# Sheet1.net
KiCad netlist of a schematic drawn in Altium Designer
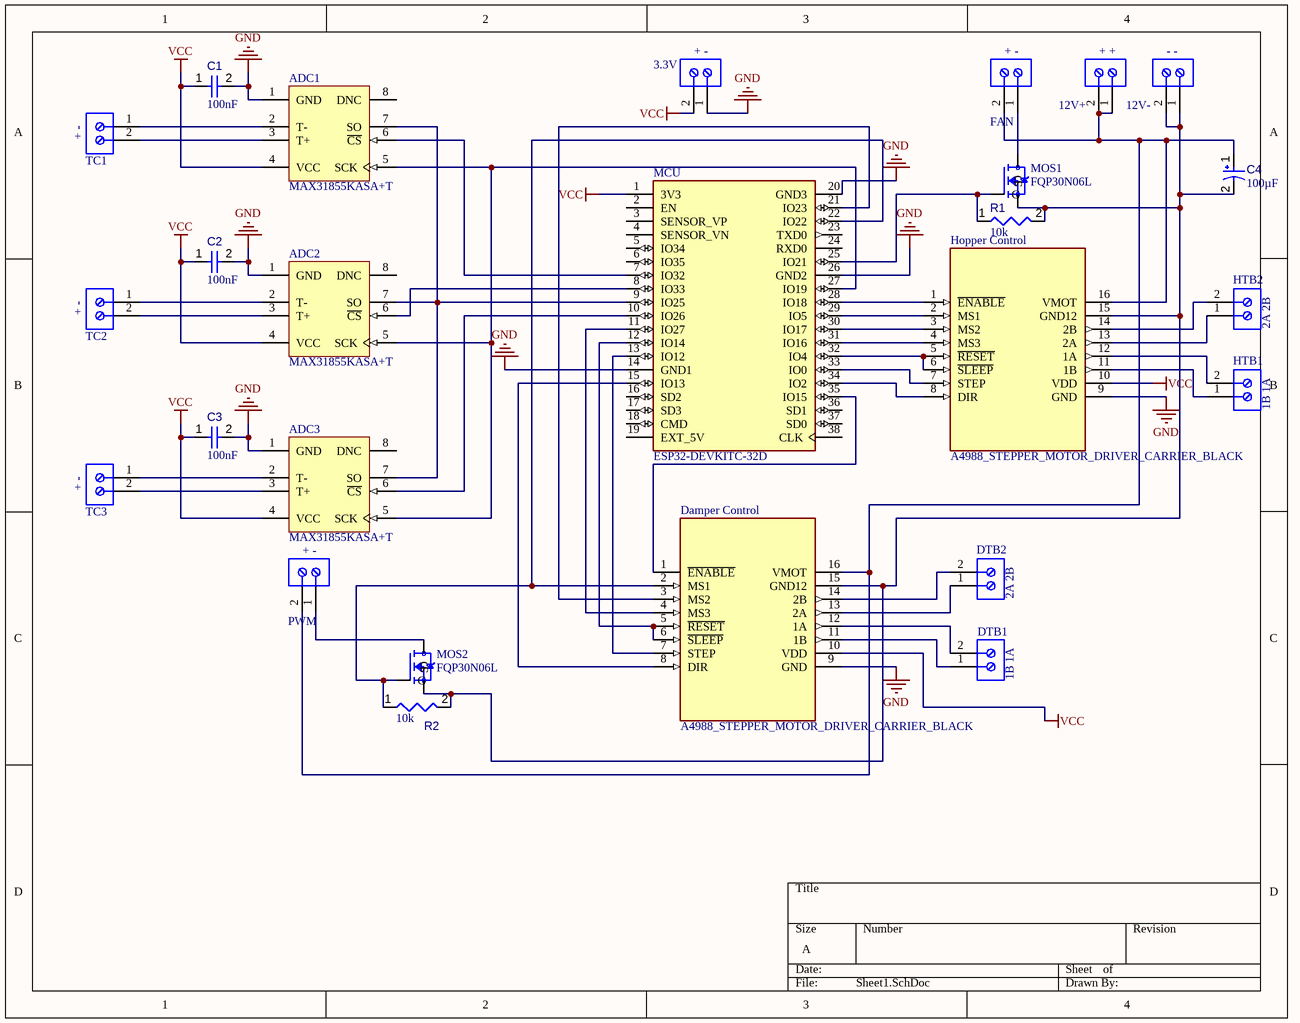
[diagram p0: Sheet1.SchDoc]

(export (version "E")
  (design (tool "Eeschema 10.0.6"))
  (components
    (comp (ref "3.3V")
      (value "+ -")
      (footprint "691103110002")
      (description "Series 1031 - 3.50 mm Horizontal Entry Modular with Pressure Clamp WR-TBL, 2 pin")
      (fields
        (field (name "MANUFACTURER") "Wurth Elektronik")
        (field (name "PART NUMBER") "691103110002")
        (field (name "PUBLISHER") "WurthElektronik")
      )
      (libsource (lib "Altium Content Vault") (part "WE-CN-1P-F-TB2"))
    )
    (comp (ref "12V+")
      (value "+ +")
      (footprint "691103110002")
      (description "Series 1031 - 3.50 mm Horizontal Entry Modular with Pressure Clamp WR-TBL, 2 pin")
      (fields
        (field (name "MANUFACTURER") "Wurth Elektronik")
        (field (name "PART NUMBER") "691103110002")
        (field (name "PUBLISHER") "WurthElektronik")
      )
      (libsource (lib "Altium Content Vault") (part "WE-CN-1P-F-TB2"))
    )
    (comp (ref "12V-")
      (value "- -")
      (footprint "691103110002")
      (description "Series 1031 - 3.50 mm Horizontal Entry Modular with Pressure Clamp WR-TBL, 2 pin")
      (fields
        (field (name "MANUFACTURER") "Wurth Elektronik")
        (field (name "PART NUMBER") "691103110002")
        (field (name "PUBLISHER") "WurthElektronik")
      )
      (libsource (lib "Altium Content Vault") (part "WE-CN-1P-F-TB2"))
    )
    (comp (ref "ADC1")
      (value "MAX31855KASA+T")
      (footprint "MAXM-S8+4_N")
      (fields (field (name "GENERIC PART NUMBER") "MAX31855"))
      (libsource (lib "Maxim Sensors") (part "MAX31855KASA+T"))
    )
    (comp (ref "ADC2")
      (value "MAX31855KASA+T")
      (footprint "MAXM-S8+4_N")
      (fields (field (name "GENERIC PART NUMBER") "MAX31855"))
      (libsource (lib "Maxim Sensors") (part "MAX31855KASA+T"))
    )
    (comp (ref "ADC3")
      (value "MAX31855KASA+T")
      (footprint "MAXM-S8+4_N")
      (fields (field (name "GENERIC PART NUMBER") "MAX31855"))
      (libsource (lib "Maxim Sensors") (part "MAX31855KASA+T"))
    )
    (comp (ref "C1")
      (value "100nF")
      (footprint "CAPC2013X95X50LL10T25")
      (description "Chip Capacitor, 100 nF, +/- 10%, 50 V, 0805 (2012 Metric)")
      (fields (field (name "TOLERANCE") "10%") (field (name "Comment") "Capacitor 100 nF +/-10% 50 V 0805"))
      (libsource (lib "IoT Pitmaster") (part "CAP-NP-2"))
    )
    (comp (ref "C2")
      (value "100nF")
      (footprint "CAPC2013X95X50LL10T25")
      (description "Chip Capacitor, 100 nF, +/- 10%, 50 V, 0805 (2012 Metric)")
      (fields (field (name "TOLERANCE") "10%") (field (name "Comment") "Capacitor 100 nF +/-10% 50 V 0805"))
      (libsource (lib "IoT Pitmaster") (part "CAP-NP-2"))
    )
    (comp (ref "C3")
      (value "100nF")
      (footprint "CAPC2013X95X50LL10T25")
      (description "Chip Capacitor, 100 nF, +/- 10%, 50 V, 0805 (2012 Metric)")
      (fields (field (name "TOLERANCE") "10%") (field (name "Comment") "Capacitor 100 nF +/-10% 50 V 0805"))
      (libsource (lib "IoT Pitmaster") (part "CAP-NP-2"))
    )
    (comp (ref "C4")
      (value "100µF")
      (footprint "CAPPR65-350-1150X800X1250")
      (description "Aluminum Electrolytic Capacitor, 100 uF, +/- 20%, 50 V, -40 to 85 degC, 2-Pin THD, RoHS, Bulk")
      (fields (field (name "MANUFACTURER") "Panasonic") (field (name "TOLERANCE") "20%"))
      (libsource (lib "IoT Pitmaster") (part "CAP-P-2"))
    )
    (comp (ref "Damper Control")
      (value "A4988_STEPPER_MOTOR_DRIVER_CARRIER_BLACK")
      (footprint "MODULE_A4988_STEPPER_MOTOR_DRIVER_CARRIER_BLACK")
      (description "Stepper motor controler; IC: A4988; 1A; Uin mot: 8Ã·35V")
      (fields (field (name "MF") "{'manufacturer': u'Pololu'}"))
      (libsource (lib "SnapEDA_Library") (part "A4988_STEPPER_MOTOR_DRIVER_CARRIER_BLACK"))
    )
    (comp (ref "DTB1")
      (value "1B 1A")
      (footprint "691103110002")
      (description "Series 1031 - 3.50 mm Horizontal Entry Modular with Pressure Clamp WR-TBL, 2 pin")
      (fields
        (field (name "MANUFACTURER") "Wurth Elektronik")
        (field (name "PART NUMBER") "691103110002")
        (field (name "PUBLISHER") "WurthElektronik")
      )
      (libsource (lib "Altium Content Vault") (part "WE-CN-1P-F-TB2"))
    )
    (comp (ref "DTB2")
      (value "2A 2B")
      (footprint "691103110002")
      (description "Series 1031 - 3.50 mm Horizontal Entry Modular with Pressure Clamp WR-TBL, 2 pin")
      (fields
        (field (name "MANUFACTURER") "Wurth Elektronik")
        (field (name "PART NUMBER") "691103110002")
        (field (name "PUBLISHER") "WurthElektronik")
      )
      (libsource (lib "Altium Content Vault") (part "WE-CN-1P-F-TB2"))
    )
    (comp (ref "FAN")
      (value "+ -")
      (footprint "691103110002")
      (description "Series 1031 - 3.50 mm Horizontal Entry Modular with Pressure Clamp WR-TBL, 2 pin")
      (fields
        (field (name "MANUFACTURER") "Wurth Elektronik")
        (field (name "PART NUMBER") "691103110002")
        (field (name "PUBLISHER") "WurthElektronik")
      )
      (libsource (lib "Altium Content Vault") (part "WE-CN-1P-F-TB2"))
    )
    (comp (ref "Hopper Control")
      (value "A4988_STEPPER_MOTOR_DRIVER_CARRIER_BLACK")
      (footprint "MODULE_A4988_STEPPER_MOTOR_DRIVER_CARRIER_BLACK")
      (description "Stepper motor controler; IC: A4988; 1A; Uin mot: 8Ã·35V")
      (fields (field (name "MF") "{'manufacturer': u'Pololu'}"))
      (libsource (lib "SnapEDA_Library") (part "A4988_STEPPER_MOTOR_DRIVER_CARRIER_BLACK"))
    )
    (comp (ref "HTB1")
      (value "1B 1A")
      (footprint "691103110002")
      (description "Series 1031 - 3.50 mm Horizontal Entry Modular with Pressure Clamp WR-TBL, 2 pin")
      (fields
        (field (name "MANUFACTURER") "Wurth Elektronik")
        (field (name "PART NUMBER") "691103110002")
        (field (name "PUBLISHER") "WurthElektronik")
      )
      (libsource (lib "Altium Content Vault") (part "WE-CN-1P-F-TB2"))
    )
    (comp (ref "HTB2")
      (value "2A 2B")
      (footprint "691103110002")
      (description "Series 1031 - 3.50 mm Horizontal Entry Modular with Pressure Clamp WR-TBL, 2 pin")
      (fields
        (field (name "MANUFACTURER") "Wurth Elektronik")
        (field (name "PART NUMBER") "691103110002")
        (field (name "PUBLISHER") "WurthElektronik")
      )
      (libsource (lib "Altium Content Vault") (part "WE-CN-1P-F-TB2"))
    )
    (comp (ref "MCU")
      (value "ESP32-DEVKITC-32D")
      (footprint "ESP32-DEVKITC-32D:MODULE_ESP32-DEVKITC-32D")
      (description "Eval Board For Esp-Wroom-32")
      (fields (field (name "MF") "{'manufacturer': u'Espressif Systems'}"))
      (libsource (lib "ESP32-DEVKITC-32D") (part "ESP32-DEVKITC-32D"))
    )
    (comp (ref "MOS1")
      (value "FQP30N06L")
      (footprint "FQP30N06L:TO220V")
      (fields (field (name "MF") "{'manufacturer': u'ON Semiconductor'}"))
      (libsource (lib "FQP30N06L") (part "FQP30N06L"))
    )
    (comp (ref "MOS2")
      (value "FQP30N06L")
      (footprint "FQP30N06L:TO220V")
      (fields (field (name "MF") "{'manufacturer': u'ON Semiconductor'}"))
      (libsource (lib "FQP30N06L") (part "FQP30N06L"))
    )
    (comp (ref "PWM")
      (value "+ -")
      (footprint "691103110002")
      (description "Series 1031 - 3.50 mm Horizontal Entry Modular with Pressure Clamp WR-TBL, 2 pin")
      (fields
        (field (name "MANUFACTURER") "Wurth Elektronik")
        (field (name "PART NUMBER") "691103110002")
        (field (name "PUBLISHER") "WurthElektronik")
      )
      (libsource (lib "Altium Content Vault") (part "WE-CN-1P-F-TB2"))
    )
    (comp (ref "R1")
      (value "10k")
      (footprint "RESC2013X50X35ML15T15")
      (description "Chip Resistor, 10 KOhm, +/- 1%, 125 mW, -55 to 155 degC, 0805 (2012 Metric)")
      (fields (field (name "TOLERANCE") "1%") (field (name "POWER") "125mW"))
      (libsource (lib "IoT Pitmaster") (part "RES-2"))
    )
    (comp (ref "R2")
      (value "10k")
      (footprint "RESC2013X50X35ML15T15")
      (description "Chip Resistor, 10 KOhm, +/- 1%, 125 mW, -55 to 155 degC, 0805 (2012 Metric)")
      (fields (field (name "TOLERANCE") "1%") (field (name "POWER") "125mW"))
      (libsource (lib "IoT Pitmaster") (part "RES-2"))
    )
    (comp (ref "TC1")
      (value "+ -")
      (footprint "691103110002")
      (description "Series 1031 - 3.50 mm Horizontal Entry Modular with Pressure Clamp WR-TBL, 2 pin")
      (fields
        (field (name "MANUFACTURER") "Wurth Elektronik")
        (field (name "PART NUMBER") "691103110002")
        (field (name "PUBLISHER") "WurthElektronik")
      )
      (libsource (lib "Altium Content Vault") (part "WE-CN-1P-F-TB2"))
    )
    (comp (ref "TC2")
      (value "+ -")
      (footprint "691103110002")
      (description "Series 1031 - 3.50 mm Horizontal Entry Modular with Pressure Clamp WR-TBL, 2 pin")
      (fields
        (field (name "MANUFACTURER") "Wurth Elektronik")
        (field (name "PART NUMBER") "691103110002")
        (field (name "PUBLISHER") "WurthElektronik")
      )
      (libsource (lib "Altium Content Vault") (part "WE-CN-1P-F-TB2"))
    )
    (comp (ref "TC3")
      (value "+ -")
      (footprint "691103110002")
      (description "Series 1031 - 3.50 mm Horizontal Entry Modular with Pressure Clamp WR-TBL, 2 pin")
      (fields
        (field (name "MANUFACTURER") "Wurth Elektronik")
        (field (name "PART NUMBER") "691103110002")
        (field (name "PUBLISHER") "WurthElektronik")
      )
      (libsource (lib "Altium Content Vault") (part "WE-CN-1P-F-TB2"))
    )
  )
  (nets
    (net (code "1") (name "GND") (class "Default")
      (node (ref "3.3V") (pin "1") (pinfunction "1_1") (pintype "passive"))
      (node (ref "ADC1") (pin "1") (pinfunction "GND_1") (pintype "power_in"))
      (node (ref "ADC2") (pin "1") (pinfunction "GND_1") (pintype "power_in"))
      (node (ref "ADC3") (pin "1") (pinfunction "GND_1") (pintype "power_in"))
      (node (ref "C1") (pin "2") (pinfunction "2_2") (pintype "passive"))
      (node (ref "C2") (pin "2") (pinfunction "2_2") (pintype "passive"))
      (node (ref "C3") (pin "2") (pinfunction "2_2") (pintype "passive"))
      (node (ref "Damper Control") (pin "9") (pinfunction "GND_9") (pintype "power_in"))
      (node (ref "Hopper Control") (pin "9") (pinfunction "GND_9") (pintype "power_in"))
      (node (ref "MCU") (pin "14") (pinfunction "GND1_14") (pintype "power_in"))
      (node (ref "MCU") (pin "20") (pinfunction "GND3_20") (pintype "power_in"))
      (node (ref "MCU") (pin "26") (pinfunction "GND2_26") (pintype "power_in"))
    )
    (net (code "2") (name "Net-(ADC1-SCK)") (class "Default")
      (node (ref "ADC1") (pin "5") (pinfunction "SCK_5") (pintype "input"))
      (node (ref "ADC2") (pin "5") (pinfunction "SCK_5") (pintype "input"))
      (node (ref "ADC3") (pin "5") (pinfunction "SCK_5") (pintype "input"))
      (node (ref "MCU") (pin "27") (pinfunction "IO19_27") (pintype "bidirectional"))
    )
    (net (code "3") (name "Net-(ADC1-SO)") (class "Default")
      (node (ref "ADC1") (pin "7") (pinfunction "SO_7") (pintype "passive"))
      (node (ref "ADC2") (pin "7") (pinfunction "SO_7") (pintype "passive"))
      (node (ref "ADC3") (pin "7") (pinfunction "SO_7") (pintype "passive"))
      (node (ref "MCU") (pin "9") (pinfunction "IO25_9") (pintype "bidirectional"))
    )
    (net (code "4") (name "Net-(ADC1-T+)") (class "Default")
      (node (ref "ADC1") (pin "3") (pinfunction "T+_3") (pintype "passive"))
      (node (ref "TC1") (pin "2") (pinfunction "2_2") (pintype "passive"))
    )
    (net (code "5") (name "Net-(ADC1-T-)") (class "Default")
      (node (ref "ADC1") (pin "2") (pinfunction "T-_2") (pintype "passive"))
      (node (ref "TC1") (pin "1") (pinfunction "1_1") (pintype "passive"))
    )
    (net (code "6") (name "Net-(ADC1-~{CS})") (class "Default")
      (node (ref "ADC1") (pin "6") (pinfunction "~{CS}_6") (pintype "input"))
      (node (ref "MCU") (pin "7") (pinfunction "IO32_7") (pintype "bidirectional"))
    )
    (net (code "7") (name "Net-(ADC2-T+)") (class "Default")
      (node (ref "ADC2") (pin "3") (pinfunction "T+_3") (pintype "passive"))
      (node (ref "TC2") (pin "2") (pinfunction "2_2") (pintype "passive"))
    )
    (net (code "8") (name "Net-(ADC2-T-)") (class "Default")
      (node (ref "ADC2") (pin "2") (pinfunction "T-_2") (pintype "passive"))
      (node (ref "TC2") (pin "1") (pinfunction "1_1") (pintype "passive"))
    )
    (net (code "9") (name "Net-(ADC2-~{CS})") (class "Default")
      (node (ref "ADC2") (pin "6") (pinfunction "~{CS}_6") (pintype "input"))
      (node (ref "MCU") (pin "8") (pinfunction "IO33_8") (pintype "bidirectional"))
    )
    (net (code "10") (name "Net-(ADC3-T+)") (class "Default")
      (node (ref "ADC3") (pin "3") (pinfunction "T+_3") (pintype "passive"))
      (node (ref "TC3") (pin "2") (pinfunction "2_2") (pintype "passive"))
    )
    (net (code "11") (name "Net-(ADC3-T-)") (class "Default")
      (node (ref "ADC3") (pin "2") (pinfunction "T-_2") (pintype "passive"))
      (node (ref "TC3") (pin "1") (pinfunction "1_1") (pintype "passive"))
    )
    (net (code "12") (name "Net-(ADC3-~{CS})") (class "Default")
      (node (ref "ADC3") (pin "6") (pinfunction "~{CS}_6") (pintype "input"))
      (node (ref "MCU") (pin "10") (pinfunction "IO26_10") (pintype "bidirectional"))
    )
    (net (code "13") (name "Net-(Damper Control-1A)") (class "Default")
      (node (ref "DTB1") (pin "2") (pinfunction "2_2") (pintype "passive"))
      (node (ref "Damper Control") (pin "12") (pinfunction "1A_12") (pintype "output"))
    )
    (net (code "14") (name "Net-(Damper Control-1B)") (class "Default")
      (node (ref "DTB1") (pin "1") (pinfunction "1_1") (pintype "passive"))
      (node (ref "Damper Control") (pin "11") (pinfunction "1B_11") (pintype "output"))
    )
    (net (code "15") (name "Net-(Damper Control-2A)") (class "Default")
      (node (ref "DTB2") (pin "1") (pinfunction "1_1") (pintype "passive"))
      (node (ref "Damper Control") (pin "13") (pinfunction "2A_13") (pintype "output"))
    )
    (net (code "16") (name "Net-(Damper Control-2B)") (class "Default")
      (node (ref "DTB2") (pin "2") (pinfunction "2_2") (pintype "passive"))
      (node (ref "Damper Control") (pin "14") (pinfunction "2B_14") (pintype "output"))
    )
    (net (code "17") (name "Net-(Damper Control-DIR)") (class "Default")
      (node (ref "Damper Control") (pin "8") (pinfunction "DIR_8") (pintype "input"))
      (node (ref "MCU") (pin "15") (pinfunction "IO13_15") (pintype "bidirectional"))
    )
    (net (code "18") (name "Net-(Damper Control-GND12)") (class "Default")
      (node (ref "12V-") (pin "1") (pinfunction "1_1") (pintype "passive"))
      (node (ref "12V-") (pin "2") (pinfunction "2_2") (pintype "passive"))
      (node (ref "C4") (pin "2") (pinfunction "2_2") (pintype "passive"))
      (node (ref "Damper Control") (pin "15") (pinfunction "GND12_15") (pintype "power_in"))
      (node (ref "Hopper Control") (pin "15") (pinfunction "GND12_15") (pintype "power_in"))
      (node (ref "MOS1") (pin "3") (pinfunction "S_3") (pintype "passive"))
      (node (ref "MOS2") (pin "3") (pinfunction "S_3") (pintype "passive"))
      (node (ref "R1") (pin "2") (pinfunction "2_2") (pintype "passive"))
      (node (ref "R2") (pin "2") (pinfunction "2_2") (pintype "passive"))
    )
    (net (code "19") (name "Net-(Damper Control-MS1)") (class "Default")
      (node (ref "Damper Control") (pin "2") (pinfunction "MS1_2") (pintype "input"))
      (node (ref "MCU") (pin "22") (pinfunction "IO22_22") (pintype "bidirectional"))
      (node (ref "MOS2") (pin "1") (pinfunction "G_1") (pintype "passive"))
      (node (ref "R2") (pin "1") (pinfunction "1_1") (pintype "passive"))
    )
    (net (code "20") (name "Net-(Damper Control-MS2)") (class "Default")
      (node (ref "Damper Control") (pin "3") (pinfunction "MS2_3") (pintype "input"))
      (node (ref "MCU") (pin "21") (pinfunction "IO23_21") (pintype "bidirectional"))
    )
    (net (code "21") (name "Net-(Damper Control-MS3)") (class "Default")
      (node (ref "Damper Control") (pin "4") (pinfunction "MS3_4") (pintype "input"))
      (node (ref "MCU") (pin "11") (pinfunction "IO27_11") (pintype "bidirectional"))
    )
    (net (code "22") (name "Net-(Damper Control-STEP)") (class "Default")
      (node (ref "Damper Control") (pin "7") (pinfunction "STEP_7") (pintype "input"))
      (node (ref "MCU") (pin "13") (pinfunction "IO12_13") (pintype "bidirectional"))
    )
    (net (code "23") (name "Net-(Damper Control-VMOT)") (class "Default")
      (node (ref "12V+") (pin "1") (pinfunction "1_1") (pintype "passive"))
      (node (ref "12V+") (pin "2") (pinfunction "2_2") (pintype "passive"))
      (node (ref "C4") (pin "1") (pinfunction "1_1") (pintype "passive"))
      (node (ref "Damper Control") (pin "16") (pinfunction "VMOT_16") (pintype "power_in"))
      (node (ref "FAN") (pin "2") (pinfunction "2_2") (pintype "passive"))
      (node (ref "Hopper Control") (pin "16") (pinfunction "VMOT_16") (pintype "power_in"))
      (node (ref "PWM") (pin "2") (pinfunction "2_2") (pintype "passive"))
    )
    (net (code "24") (name "Net-(Damper Control-~{ENABLE})") (class "Default")
      (node (ref "Damper Control") (pin "1") (pinfunction "~{ENABLE}_1") (pintype "passive"))
      (node (ref "MCU") (pin "35") (pinfunction "IO15_35") (pintype "bidirectional"))
    )
    (net (code "25") (name "Net-(Damper Control-~{RESET})") (class "Default")
      (node (ref "Damper Control") (pin "5") (pinfunction "~{RESET}_5") (pintype "input"))
      (node (ref "Damper Control") (pin "6") (pinfunction "~{SLEEP}_6") (pintype "input"))
      (node (ref "MCU") (pin "12") (pinfunction "IO14_12") (pintype "bidirectional"))
    )
    (net (code "26") (name "Net-(Hopper Control-1A)") (class "Default")
      (node (ref "HTB1") (pin "2") (pinfunction "2_2") (pintype "passive"))
      (node (ref "Hopper Control") (pin "12") (pinfunction "1A_12") (pintype "output"))
    )
    (net (code "27") (name "Net-(Hopper Control-1B)") (class "Default")
      (node (ref "HTB1") (pin "1") (pinfunction "1_1") (pintype "passive"))
      (node (ref "Hopper Control") (pin "11") (pinfunction "1B_11") (pintype "output"))
    )
    (net (code "28") (name "Net-(Hopper Control-2A)") (class "Default")
      (node (ref "HTB2") (pin "1") (pinfunction "1_1") (pintype "passive"))
      (node (ref "Hopper Control") (pin "13") (pinfunction "2A_13") (pintype "output"))
    )
    (net (code "29") (name "Net-(Hopper Control-2B)") (class "Default")
      (node (ref "HTB2") (pin "2") (pinfunction "2_2") (pintype "passive"))
      (node (ref "Hopper Control") (pin "14") (pinfunction "2B_14") (pintype "output"))
    )
    (net (code "30") (name "Net-(Hopper Control-DIR)") (class "Default")
      (node (ref "Hopper Control") (pin "8") (pinfunction "DIR_8") (pintype "input"))
      (node (ref "MCU") (pin "34") (pinfunction "IO2_34") (pintype "bidirectional"))
    )
    (net (code "31") (name "Net-(Hopper Control-MS1)") (class "Default")
      (node (ref "Hopper Control") (pin "2") (pinfunction "MS1_2") (pintype "input"))
      (node (ref "MCU") (pin "29") (pinfunction "IO5_29") (pintype "bidirectional"))
    )
    (net (code "32") (name "Net-(Hopper Control-MS2)") (class "Default")
      (node (ref "Hopper Control") (pin "3") (pinfunction "MS2_3") (pintype "input"))
      (node (ref "MCU") (pin "30") (pinfunction "IO17_30") (pintype "bidirectional"))
    )
    (net (code "33") (name "Net-(Hopper Control-MS3)") (class "Default")
      (node (ref "Hopper Control") (pin "4") (pinfunction "MS3_4") (pintype "input"))
      (node (ref "MCU") (pin "31") (pinfunction "IO16_31") (pintype "bidirectional"))
    )
    (net (code "34") (name "Net-(Hopper Control-STEP)") (class "Default")
      (node (ref "Hopper Control") (pin "7") (pinfunction "STEP_7") (pintype "input"))
      (node (ref "MCU") (pin "33") (pinfunction "IO0_33") (pintype "bidirectional"))
    )
    (net (code "35") (name "Net-(Hopper Control-~{ENABLE})") (class "Default")
      (node (ref "Hopper Control") (pin "1") (pinfunction "~{ENABLE}_1") (pintype "passive"))
      (node (ref "MCU") (pin "28") (pinfunction "IO18_28") (pintype "bidirectional"))
    )
    (net (code "36") (name "Net-(Hopper Control-~{RESET})") (class "Default")
      (node (ref "Hopper Control") (pin "5") (pinfunction "~{RESET}_5") (pintype "input"))
      (node (ref "Hopper Control") (pin "6") (pinfunction "~{SLEEP}_6") (pintype "input"))
      (node (ref "MCU") (pin "32") (pinfunction "IO4_32") (pintype "bidirectional"))
    )
    (net (code "37") (name "Net-(MCU-IO21)") (class "Default")
      (node (ref "MCU") (pin "25") (pinfunction "IO21_25") (pintype "bidirectional"))
      (node (ref "MOS1") (pin "1") (pinfunction "G_1") (pintype "passive"))
      (node (ref "R1") (pin "1") (pinfunction "1_1") (pintype "passive"))
    )
    (net (code "38") (name "Net-(MOS1-D)") (class "Default")
      (node (ref "FAN") (pin "1") (pinfunction "1_1") (pintype "passive"))
      (node (ref "MOS1") (pin "2") (pinfunction "D_2") (pintype "passive"))
    )
    (net (code "39") (name "Net-(MOS2-D)") (class "Default")
      (node (ref "MOS2") (pin "2") (pinfunction "D_2") (pintype "passive"))
      (node (ref "PWM") (pin "1") (pinfunction "1_1") (pintype "passive"))
    )
    (net (code "40") (name "VCC") (class "Default")
      (node (ref "3.3V") (pin "2") (pinfunction "2_2") (pintype "passive"))
      (node (ref "ADC1") (pin "4") (pinfunction "VCC_4") (pintype "power_in"))
      (node (ref "ADC2") (pin "4") (pinfunction "VCC_4") (pintype "power_in"))
      (node (ref "ADC3") (pin "4") (pinfunction "VCC_4") (pintype "power_in"))
      (node (ref "C1") (pin "1") (pinfunction "1_1") (pintype "passive"))
      (node (ref "C2") (pin "1") (pinfunction "1_1") (pintype "passive"))
      (node (ref "C3") (pin "1") (pinfunction "1_1") (pintype "passive"))
      (node (ref "Damper Control") (pin "10") (pinfunction "VDD_10") (pintype "power_in"))
      (node (ref "Hopper Control") (pin "10") (pinfunction "VDD_10") (pintype "power_in"))
      (node (ref "MCU") (pin "1") (pinfunction "3V3_1") (pintype "power_in"))
    )
    (net (code "41") (name "unconnected-(ADC1-DNC-Pad8)") (class "Default")
      (node (ref "ADC1") (pin "8") (pinfunction "DNC_8") (pintype "passive"))
    )
    (net (code "42") (name "unconnected-(ADC2-DNC-Pad8)") (class "Default")
      (node (ref "ADC2") (pin "8") (pinfunction "DNC_8") (pintype "passive"))
    )
    (net (code "43") (name "unconnected-(ADC3-DNC-Pad8)") (class "Default")
      (node (ref "ADC3") (pin "8") (pinfunction "DNC_8") (pintype "passive"))
    )
    (net (code "44") (name "unconnected-(MCU-CLK-Pad38)") (class "Default")
      (node (ref "MCU") (pin "38") (pinfunction "CLK_38") (pintype "passive"))
    )
    (net (code "45") (name "unconnected-(MCU-CMD-Pad18)") (class "Default")
      (node (ref "MCU") (pin "18") (pinfunction "CMD_18") (pintype "bidirectional"))
    )
    (net (code "46") (name "unconnected-(MCU-EN-Pad2)") (class "Default")
      (node (ref "MCU") (pin "2") (pinfunction "EN_2") (pintype "passive"))
    )
    (net (code "47") (name "unconnected-(MCU-EXT_5V-Pad19)") (class "Default")
      (node (ref "MCU") (pin "19") (pinfunction "EXT_5V_19") (pintype "power_in"))
    )
    (net (code "48") (name "unconnected-(MCU-IO34-Pad5)") (class "Default")
      (node (ref "MCU") (pin "5") (pinfunction "IO34_5") (pintype "bidirectional"))
    )
    (net (code "49") (name "unconnected-(MCU-IO35-Pad6)") (class "Default")
      (node (ref "MCU") (pin "6") (pinfunction "IO35_6") (pintype "bidirectional"))
    )
    (net (code "50") (name "unconnected-(MCU-RXD0-Pad24)") (class "Default")
      (node (ref "MCU") (pin "24") (pinfunction "RXD0_24") (pintype "passive"))
    )
    (net (code "51") (name "unconnected-(MCU-SD0-Pad37)") (class "Default")
      (node (ref "MCU") (pin "37") (pinfunction "SD0_37") (pintype "bidirectional"))
    )
    (net (code "52") (name "unconnected-(MCU-SD1-Pad36)") (class "Default")
      (node (ref "MCU") (pin "36") (pinfunction "SD1_36") (pintype "bidirectional"))
    )
    (net (code "53") (name "unconnected-(MCU-SD2-Pad16)") (class "Default")
      (node (ref "MCU") (pin "16") (pinfunction "SD2_16") (pintype "bidirectional"))
    )
    (net (code "54") (name "unconnected-(MCU-SD3-Pad17)") (class "Default")
      (node (ref "MCU") (pin "17") (pinfunction "SD3_17") (pintype "bidirectional"))
    )
    (net (code "55") (name "unconnected-(MCU-SENSOR_VN-Pad4)") (class "Default")
      (node (ref "MCU") (pin "4") (pinfunction "SENSOR_VN_4") (pintype "passive"))
    )
    (net (code "56") (name "unconnected-(MCU-SENSOR_VP-Pad3)") (class "Default")
      (node (ref "MCU") (pin "3") (pinfunction "SENSOR_VP_3") (pintype "passive"))
    )
    (net (code "57") (name "unconnected-(MCU-TXD0-Pad23)") (class "Default")
      (node (ref "MCU") (pin "23") (pinfunction "TXD0_23") (pintype "output"))
    )
  )
)
